# memory.net
KiCad netlist of a schematic drawn in Altium Designer
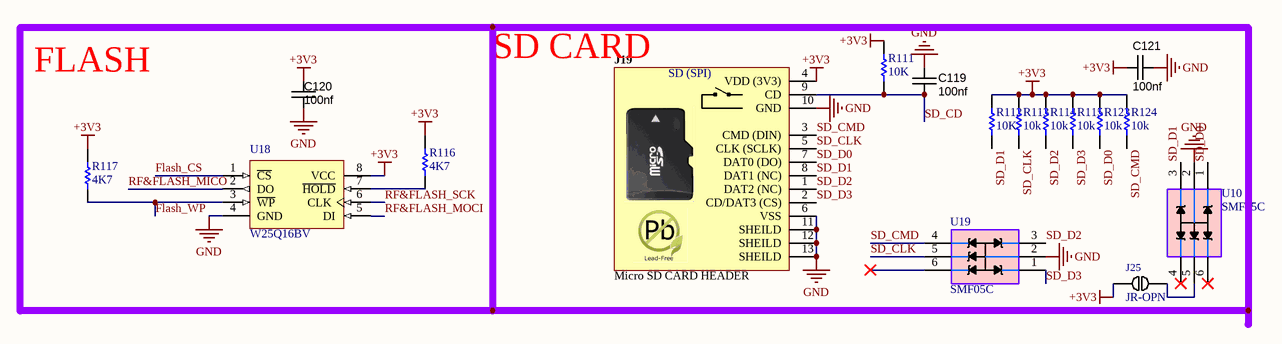
[diagram p0: memory.SchDoc]

(export (version "E")
  (design (tool "Eeschema 10.0.6"))
  (components
    (comp (ref "C119")
      (value "100nf")
      (footprint "CAPC1608X90N")
      (description "Capacitor SMD Cer 100nF 10% 50V X7R 0603")
      (fields (field (name "TOLERANCE") "±10%"))
      (libsource (lib "altium-import") (part "root_0_CAPC_100n_0603_X7R_50V_10%_"))
    )
    (comp (ref "C120")
      (value "100nf")
      (footprint "CAPC1608X90N")
      (description "Capacitor SMD Cer 100nF 10% 50V X7R 0603")
      (fields (field (name "TOLERANCE") "±10%"))
      (libsource (lib "altium-import") (part "root_2_CAPC_100n_0603_X7R_50V_10%_"))
    )
    (comp (ref "C121")
      (value "100nf")
      (footprint "CAPC1608X90N")
      (description "Capacitor SMD Cer 100nF 10% 50V X7R 0603")
      (fields (field (name "TOLERANCE") "±10%"))
      (libsource (lib "altium-import") (part "root_3_CAPC_100n_0603_X7R_50V_10%_"))
    )
    (comp (ref "J19")
      (value "Micro SD CARD HEADER")
      (footprint "SMD_CON_Micro SD -Push-Push")
      (description "Secure Digital Card Socket")
      (fields (field (name "DESIGNER") "Eng. Saeid Jorablo") (field (name "PUBLISHER") "SJ UnLimited"))
      (libsource (lib "SJ Sockets & Connectors (1)") (part "CON_Micro SD"))
    )
    (comp (ref "J25") (value "JR-OPN") (description "SOLDERDOT BYPASS") (libsource (lib "*") (part "BYPASS")))
    (comp (ref "R111")
      (value "10K")
      (footprint "Resistor_SMD_0603 (1608)")
      (description "Resistor 0603")
      (fields (field (name "PUBLISHER") "Seyed Razi Vesali") (field (name "EMAIL") "razi.vesali@gmail.com"))
      (libsource (lib "resistors") (part "Resistor"))
    )
    (comp (ref "R112")
      (value "10K")
      (footprint "Resistor_SMD_0603 (1608)")
      (description "Resistor 0603")
      (fields (field (name "PUBLISHER") "Seyed Razi Vesali") (field (name "EMAIL") "razi.vesali@gmail.com"))
      (libsource (lib "resistors") (part "Resistor"))
    )
    (comp (ref "R113")
      (value "10k")
      (footprint "Resistor_SMD_0603 (1608)")
      (description "Resistor 0603")
      (fields (field (name "PUBLISHER") "Seyed Razi Vesali") (field (name "EMAIL") "razi.vesali@gmail.com"))
      (libsource (lib "resistors") (part "Resistor"))
    )
    (comp (ref "R114")
      (value "10k")
      (footprint "Resistor_SMD_0603 (1608)")
      (description "Resistor 0603")
      (fields (field (name "PUBLISHER") "Seyed Razi Vesali") (field (name "EMAIL") "razi.vesali@gmail.com"))
      (libsource (lib "resistors") (part "Resistor"))
    )
    (comp (ref "R115")
      (value "10k")
      (footprint "Resistor_SMD_0603 (1608)")
      (description "Resistor 0603")
      (fields (field (name "PUBLISHER") "Seyed Razi Vesali") (field (name "EMAIL") "razi.vesali@gmail.com"))
      (libsource (lib "resistors") (part "Resistor"))
    )
    (comp (ref "R116")
      (value "4K7")
      (footprint "Resistor_SMD_0603 (1608)")
      (description "Resistor 0603")
      (fields (field (name "PUBLISHER") "Seyed Razi Vesali") (field (name "EMAIL") "razi.vesali@gmail.com"))
      (libsource (lib "resistors") (part "Resistor"))
    )
    (comp (ref "R117")
      (value "4K7")
      (footprint "Resistor_SMD_0603 (1608)")
      (description "Resistor 0603")
      (fields (field (name "PUBLISHER") "Seyed Razi Vesali") (field (name "EMAIL") "razi.vesali@gmail.com"))
      (libsource (lib "resistors") (part "Resistor"))
    )
    (comp (ref "R123")
      (value "10k")
      (footprint "Resistor_SMD_0603 (1608)")
      (description "Resistor 0603")
      (fields (field (name "PUBLISHER") "Seyed Razi Vesali") (field (name "EMAIL") "razi.vesali@gmail.com"))
      (libsource (lib "resistors") (part "Resistor"))
    )
    (comp (ref "R124")
      (value "10k")
      (footprint "Resistor_SMD_0603 (1608)")
      (description "Resistor 0603")
      (fields (field (name "PUBLISHER") "Seyed Razi Vesali") (field (name "EMAIL") "razi.vesali@gmail.com"))
      (libsource (lib "resistors") (part "Resistor"))
    )
    (comp (ref "U10")
      (value "SMF05C")
      (footprint "SC706")
      (description "TVS Diode Array  For ESD and Latch-Up Protection")
      (libsource (lib "altium-import") (part "root_3_TVS Diode_"))
    )
    (comp (ref "U18")
      (value "W25Q16BV")
      (footprint "SO08")
      (description "Flash, pin, soic, flash, Memory, Semiconductors and Actives, serial, ic")
      (libsource (lib "altium-import") (part "root_0_W25Q16BV_"))
    )
    (comp (ref "U19")
      (value "SMF05C")
      (footprint "SC706")
      (description "TVS Diode Array  For ESD and Latch-Up Protection")
      (libsource (lib "altium-import") (part "root_2_TVS Diode_"))
    )
  )
  (nets
    (net (code "1") (name "+3V3") (class "Default")
      (node (ref "C120") (pin "2") (pintype "passive"))
      (node (ref "C121") (pin "2") (pintype "passive"))
      (node (ref "J19") (pin "4") (pinfunction "VDD_(3V3)_4") (pintype "power_in"))
      (node (ref "J25") (pin "2") (pinfunction "2_2") (pintype "passive"))
      (node (ref "R111") (pin "1") (pinfunction "1_1") (pintype "passive"))
      (node (ref "R112") (pin "1") (pinfunction "1_1") (pintype "passive"))
      (node (ref "R113") (pin "1") (pinfunction "1_1") (pintype "passive"))
      (node (ref "R114") (pin "1") (pinfunction "1_1") (pintype "passive"))
      (node (ref "R115") (pin "1") (pinfunction "1_1") (pintype "passive"))
      (node (ref "R116") (pin "1") (pinfunction "1_1") (pintype "passive"))
      (node (ref "R117") (pin "1") (pinfunction "1_1") (pintype "passive"))
      (node (ref "R123") (pin "1") (pinfunction "1_1") (pintype "passive"))
      (node (ref "R124") (pin "1") (pinfunction "1_1") (pintype "passive"))
      (node (ref "U18") (pin "8") (pinfunction "VCC_8") (pintype "power_in"))
    )
    (net (code "2") (name "/Flash_CS") (class "Default")
      (node (ref "U18") (pin "1") (pinfunction "~{CS}_1") (pintype "input"))
    )
    (net (code "3") (name "/Flash_WP") (class "Default")
      (node (ref "R117") (pin "2") (pinfunction "2_2") (pintype "passive"))
      (node (ref "U18") (pin "3") (pinfunction "~{WP}_3") (pintype "input"))
    )
    (net (code "4") (name "/RF&FLASH_MICO") (class "Default")
      (node (ref "U18") (pin "2") (pinfunction "DO_2") (pintype "output"))
    )
    (net (code "5") (name "/RF&FLASH_MOCI") (class "Default")
      (node (ref "U18") (pin "5") (pinfunction "DI_5") (pintype "input"))
    )
    (net (code "6") (name "/RF&FLASH_SCK") (class "Default")
      (node (ref "U18") (pin "6") (pinfunction "CLK_6") (pintype "input"))
    )
    (net (code "7") (name "/SD_CD") (class "Default")
      (node (ref "C119") (pin "2") (pintype "passive"))
      (node (ref "J19") (pin "9") (pinfunction "CD_9") (pintype "passive"))
      (node (ref "R111") (pin "2") (pinfunction "2_2") (pintype "passive"))
    )
    (net (code "8") (name "/SD_CLK") (class "Default")
      (node (ref "J19") (pin "5") (pinfunction "CLK_(SCLK)_5") (pintype "passive"))
      (node (ref "R113") (pin "2") (pinfunction "2_2") (pintype "passive"))
      (node (ref "U19") (pin "5") (pinfunction "L5_5") (pintype "passive"))
    )
    (net (code "9") (name "/SD_CMD") (class "Default")
      (node (ref "J19") (pin "3") (pinfunction "CMD_(DIN)_3") (pintype "passive"))
      (node (ref "R124") (pin "2") (pinfunction "2_2") (pintype "passive"))
      (node (ref "U19") (pin "4") (pinfunction "L4_4") (pintype "passive"))
    )
    (net (code "10") (name "/SD_D0") (class "Default")
      (node (ref "J19") (pin "7") (pinfunction "DAT0_(DO)_7") (pintype "passive"))
      (node (ref "R123") (pin "2") (pinfunction "2_2") (pintype "passive"))
      (node (ref "U10") (pin "1") (pinfunction "L1_1") (pintype "passive"))
    )
    (net (code "11") (name "/SD_D1") (class "Default")
      (node (ref "J19") (pin "8") (pinfunction "DAT1_(NC)_8") (pintype "passive"))
      (node (ref "R112") (pin "2") (pinfunction "2_2") (pintype "passive"))
      (node (ref "U10") (pin "3") (pinfunction "L3_3") (pintype "passive"))
    )
    (net (code "12") (name "/SD_D2") (class "Default")
      (node (ref "J19") (pin "1") (pinfunction "DAT2_(NC)_1") (pintype "passive"))
      (node (ref "R114") (pin "2") (pinfunction "2_2") (pintype "passive"))
      (node (ref "U19") (pin "3") (pinfunction "L3_3") (pintype "passive"))
    )
    (net (code "13") (name "/SD_D3") (class "Default")
      (node (ref "J19") (pin "2") (pinfunction "CD/DAT3_(CS)_2") (pintype "passive"))
      (node (ref "R115") (pin "2") (pinfunction "2_2") (pintype "passive"))
      (node (ref "U19") (pin "1") (pinfunction "L1_1") (pintype "passive"))
    )
    (net (code "14") (name "GND") (class "Default")
      (node (ref "C119") (pin "1") (pintype "passive"))
      (node (ref "C120") (pin "1") (pintype "passive"))
      (node (ref "C121") (pin "1") (pintype "passive"))
      (node (ref "J19") (pin "10") (pinfunction "GND_10") (pintype "power_in"))
      (node (ref "J19") (pin "11") (pinfunction "SHEILD_11") (pintype "power_in"))
      (node (ref "J19") (pin "12") (pinfunction "SHEILD_12") (pintype "power_in"))
      (node (ref "J19") (pin "13") (pinfunction "SHEILD_13") (pintype "power_in"))
      (node (ref "J19") (pin "6") (pinfunction "VSS_6") (pintype "power_in"))
      (node (ref "U10") (pin "2") (pinfunction "Gnd_2") (pintype "passive"))
      (node (ref "U18") (pin "4") (pinfunction "GND_4") (pintype "power_in"))
      (node (ref "U19") (pin "2") (pinfunction "Gnd_2") (pintype "passive"))
    )
    (net (code "15") (name "Net-(U10-L5)") (class "Default")
      (node (ref "J25") (pin "1") (pinfunction "1_1") (pintype "passive"))
      (node (ref "U10") (pin "5") (pinfunction "L5_5") (pintype "passive"))
    )
    (net (code "16") (name "Net-(U18-~{HOLD})") (class "Default")
      (node (ref "R116") (pin "2") (pinfunction "2_2") (pintype "passive"))
      (node (ref "U18") (pin "7") (pinfunction "~{HOLD}_7") (pintype "input"))
    )
    (net (code "17") (name "unconnected-(U10-L4-Pad4)") (class "Default")
      (node (ref "U10") (pin "4") (pinfunction "L4_4") (pintype "passive+no_connect"))
    )
    (net (code "18") (name "unconnected-(U10-L6-Pad6)") (class "Default")
      (node (ref "U10") (pin "6") (pinfunction "L6_6") (pintype "passive+no_connect"))
    )
    (net (code "19") (name "unconnected-(U19-L6-Pad6)") (class "Default")
      (node (ref "U19") (pin "6") (pinfunction "L6_6") (pintype "passive+no_connect"))
    )
  )
)
